# fpga_power.net
KiCad netlist of a schematic drawn in Altium Designer
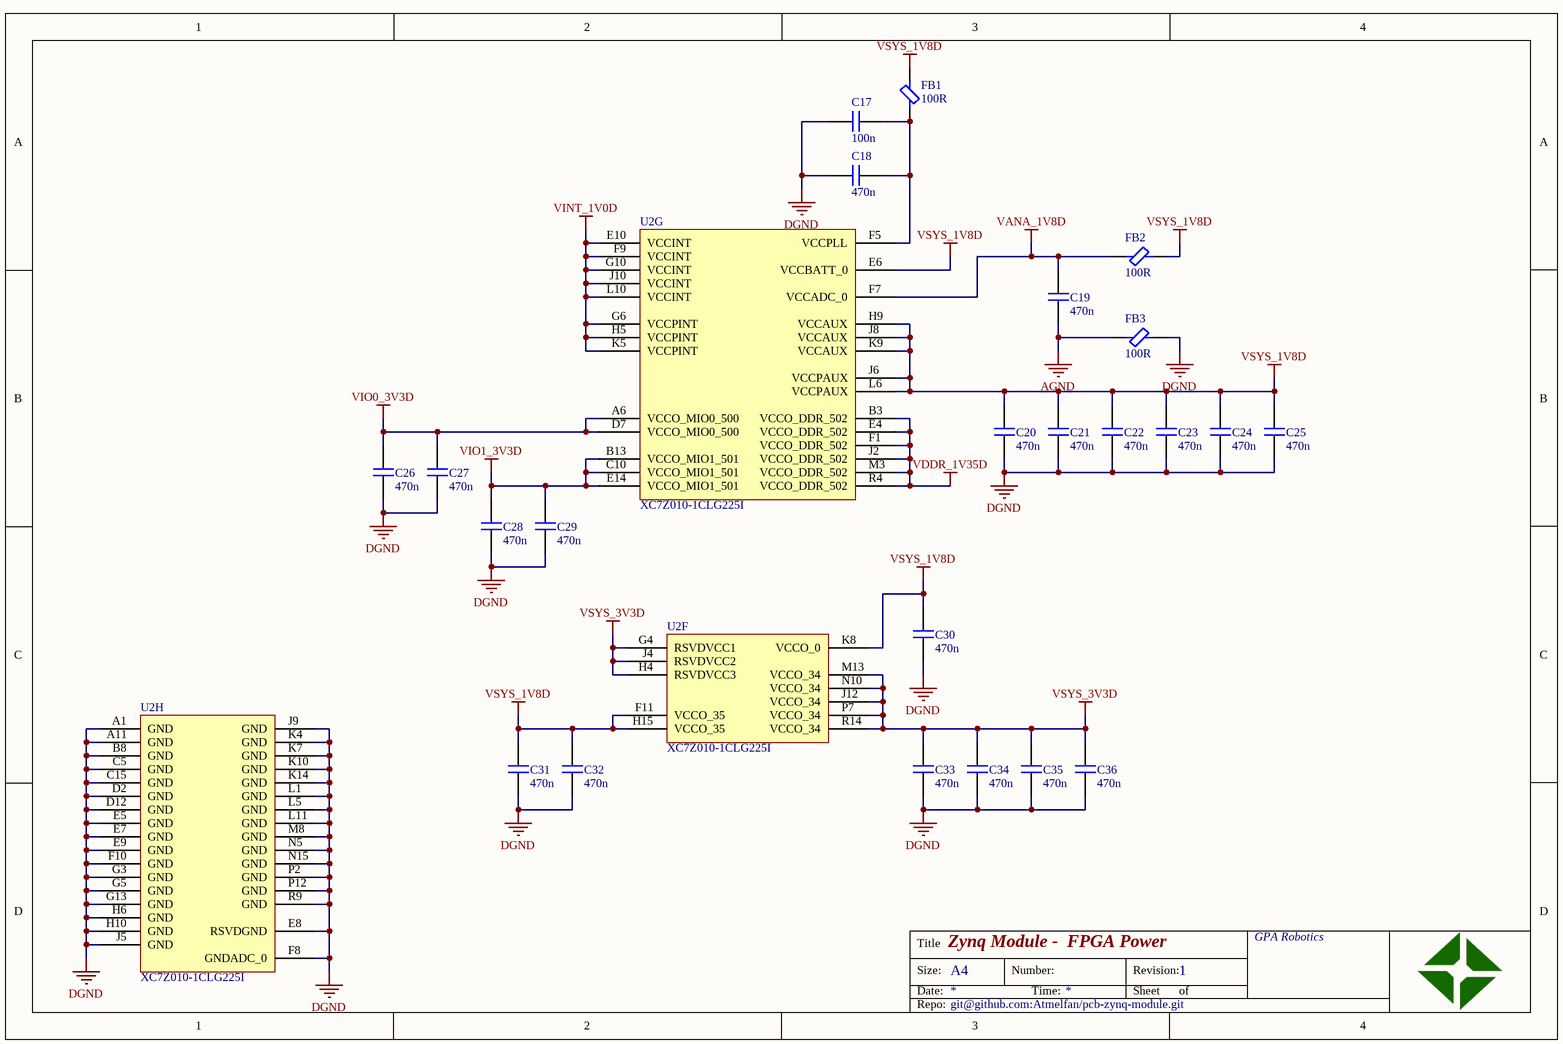
[diagram p0: fpga_power.SchDoc]

(export (version "E")
  (design (tool "Eeschema 10.0.6"))
  (components
    (comp (ref "C17")
      (value "100n")
      (footprint "CAPC2012X11N")
      (description "Capacitor")
      (fields (field (name "Comment") "cap"))
      (libsource (lib "lib_passives") (part "cap"))
    )
    (comp (ref "C18")
      (value "470n")
      (footprint "CAPC1608X08N")
      (description "Capacitor")
      (fields (field (name "Comment") "cap"))
      (libsource (lib "lib_passives") (part "cap"))
    )
    (comp (ref "C19")
      (value "470n")
      (footprint "CAPC1608X08N")
      (description "Capacitor")
      (fields (field (name "Comment") "cap"))
      (libsource (lib "lib_passives") (part "cap"))
    )
    (comp (ref "C20")
      (value "470n")
      (footprint "CAPC1608X08N")
      (description "Capacitor")
      (fields (field (name "Comment") "cap"))
      (libsource (lib "lib_passives") (part "cap"))
    )
    (comp (ref "C21")
      (value "470n")
      (footprint "CAPC1608X08N")
      (description "Capacitor")
      (fields (field (name "Comment") "cap"))
      (libsource (lib "lib_passives") (part "cap"))
    )
    (comp (ref "C22")
      (value "470n")
      (footprint "CAPC1608X08N")
      (description "Capacitor")
      (fields (field (name "Comment") "cap"))
      (libsource (lib "lib_passives") (part "cap"))
    )
    (comp (ref "C23")
      (value "470n")
      (footprint "CAPC1608X08N")
      (description "Capacitor")
      (fields (field (name "Comment") "cap"))
      (libsource (lib "lib_passives") (part "cap"))
    )
    (comp (ref "C24")
      (value "470n")
      (footprint "CAPC1608X08N")
      (description "Capacitor")
      (fields (field (name "Comment") "cap"))
      (libsource (lib "lib_passives") (part "cap"))
    )
    (comp (ref "C25")
      (value "470n")
      (footprint "CAPC1608X08N")
      (description "Capacitor")
      (fields (field (name "Comment") "cap"))
      (libsource (lib "lib_passives") (part "cap"))
    )
    (comp (ref "C26")
      (value "470n")
      (footprint "CAPC1608X08N")
      (description "Capacitor")
      (fields (field (name "Comment") "cap"))
      (libsource (lib "lib_passives") (part "cap"))
    )
    (comp (ref "C27")
      (value "470n")
      (footprint "CAPC1608X08N")
      (description "Capacitor")
      (fields (field (name "Comment") "cap"))
      (libsource (lib "lib_passives") (part "cap"))
    )
    (comp (ref "C28")
      (value "470n")
      (footprint "CAPC1608X08N")
      (description "Capacitor")
      (fields (field (name "Comment") "cap"))
      (libsource (lib "lib_passives") (part "cap"))
    )
    (comp (ref "C29")
      (value "470n")
      (footprint "CAPC1608X08N")
      (description "Capacitor")
      (fields (field (name "Comment") "cap"))
      (libsource (lib "lib_passives") (part "cap"))
    )
    (comp (ref "C30")
      (value "470n")
      (footprint "CAPC1608X08N")
      (description "Capacitor")
      (fields (field (name "Comment") "cap"))
      (libsource (lib "lib_passives") (part "cap"))
    )
    (comp (ref "C31")
      (value "470n")
      (footprint "CAPC1608X08N")
      (description "Capacitor")
      (fields (field (name "Comment") "cap"))
      (libsource (lib "lib_passives") (part "cap"))
    )
    (comp (ref "C32")
      (value "470n")
      (footprint "CAPC1608X08N")
      (description "Capacitor")
      (fields (field (name "Comment") "cap"))
      (libsource (lib "lib_passives") (part "cap"))
    )
    (comp (ref "C33")
      (value "470n")
      (footprint "CAPC1608X08N")
      (description "Capacitor")
      (fields (field (name "Comment") "cap"))
      (libsource (lib "lib_passives") (part "cap"))
    )
    (comp (ref "C34")
      (value "470n")
      (footprint "CAPC1608X08N")
      (description "Capacitor")
      (fields (field (name "Comment") "cap"))
      (libsource (lib "lib_passives") (part "cap"))
    )
    (comp (ref "C35")
      (value "470n")
      (footprint "CAPC1608X08N")
      (description "Capacitor")
      (fields (field (name "Comment") "cap"))
      (libsource (lib "lib_passives") (part "cap"))
    )
    (comp (ref "C36")
      (value "470n")
      (footprint "CAPC1608X08N")
      (description "Capacitor")
      (fields (field (name "Comment") "cap"))
      (libsource (lib "lib_passives") (part "cap"))
    )
    (comp (ref "FB1")
      (value "100R")
      (footprint "INDC1005X06N")
      (description "Inductor")
      (fields (field (name "Comment") "ferrite"))
      (libsource (lib "lib_passives") (part "ferrite"))
    )
    (comp (ref "FB2")
      (value "100R")
      (footprint "INDC1005X06N")
      (description "Inductor")
      (fields (field (name "Comment") "ferrite"))
      (libsource (lib "lib_passives") (part "ferrite"))
    )
    (comp (ref "FB3")
      (value "100R")
      (footprint "INDC1005X06N")
      (description "Inductor")
      (fields (field (name "Comment") "ferrite"))
      (libsource (lib "lib_passives") (part "ferrite"))
    )
    (comp (ref "U2")
      (value "XC7Z010-1CLG225I")
      (footprint "CLG225")
      (fields (field (name "GENERIC PART NUMBER") "XC7Z010"))
      (libsource (lib "Altium Content Vault") (part "XNLX-XC7Z010-CLG225"))
    )
  )
  (nets
    (net (code "1") (name "AGND") (class "Default")
      (node (ref "C19") (pin "1") (pinfunction "1_1") (pintype "passive"))
      (node (ref "FB3") (pin "2") (pinfunction "2_2") (pintype "passive"))
    )
    (net (code "2") (name "DGND") (class "Default")
      (node (ref "C17") (pin "1") (pinfunction "1_1") (pintype "passive"))
      (node (ref "C18") (pin "1") (pinfunction "1_1") (pintype "passive"))
      (node (ref "C20") (pin "1") (pinfunction "1_1") (pintype "passive"))
      (node (ref "C21") (pin "1") (pinfunction "1_1") (pintype "passive"))
      (node (ref "C22") (pin "1") (pinfunction "1_1") (pintype "passive"))
      (node (ref "C23") (pin "1") (pinfunction "1_1") (pintype "passive"))
      (node (ref "C24") (pin "1") (pinfunction "1_1") (pintype "passive"))
      (node (ref "C25") (pin "1") (pinfunction "1_1") (pintype "passive"))
      (node (ref "C26") (pin "1") (pinfunction "1_1") (pintype "passive"))
      (node (ref "C27") (pin "1") (pinfunction "1_1") (pintype "passive"))
      (node (ref "C28") (pin "1") (pinfunction "1_1") (pintype "passive"))
      (node (ref "C29") (pin "1") (pinfunction "1_1") (pintype "passive"))
      (node (ref "C30") (pin "1") (pinfunction "1_1") (pintype "passive"))
      (node (ref "C31") (pin "1") (pinfunction "1_1") (pintype "passive"))
      (node (ref "C32") (pin "1") (pinfunction "1_1") (pintype "passive"))
      (node (ref "C33") (pin "1") (pinfunction "1_1") (pintype "passive"))
      (node (ref "C34") (pin "1") (pinfunction "1_1") (pintype "passive"))
      (node (ref "C35") (pin "1") (pinfunction "1_1") (pintype "passive"))
      (node (ref "C36") (pin "1") (pinfunction "1_1") (pintype "passive"))
      (node (ref "FB3") (pin "1") (pinfunction "1_1") (pintype "passive"))
      (node (ref "U2") (pin "A1") (pinfunction "GND_A1") (pintype "power_in"))
      (node (ref "U2") (pin "A11") (pinfunction "GND_A11") (pintype "power_in"))
      (node (ref "U2") (pin "B8") (pinfunction "GND_B8") (pintype "power_in"))
      (node (ref "U2") (pin "C15") (pinfunction "GND_C15") (pintype "power_in"))
      (node (ref "U2") (pin "C5") (pinfunction "GND_C5") (pintype "power_in"))
      (node (ref "U2") (pin "D12") (pinfunction "GND_D12") (pintype "power_in"))
      (node (ref "U2") (pin "D2") (pinfunction "GND_D2") (pintype "power_in"))
      (node (ref "U2") (pin "E5") (pinfunction "GND_E5") (pintype "power_in"))
      (node (ref "U2") (pin "E7") (pinfunction "GND_E7") (pintype "power_in"))
      (node (ref "U2") (pin "E8") (pinfunction "RSVDGND_E8") (pintype "power_in"))
      (node (ref "U2") (pin "E9") (pinfunction "GND_E9") (pintype "power_in"))
      (node (ref "U2") (pin "F10") (pinfunction "GND_F10") (pintype "power_in"))
      (node (ref "U2") (pin "F8") (pinfunction "GNDADC_0_F8") (pintype "power_in"))
      (node (ref "U2") (pin "G13") (pinfunction "GND_G13") (pintype "power_in"))
      (node (ref "U2") (pin "G3") (pinfunction "GND_G3") (pintype "power_in"))
      (node (ref "U2") (pin "G5") (pinfunction "GND_G5") (pintype "power_in"))
      (node (ref "U2") (pin "H10") (pinfunction "GND_H10") (pintype "power_in"))
      (node (ref "U2") (pin "H6") (pinfunction "GND_H6") (pintype "power_in"))
      (node (ref "U2") (pin "J5") (pinfunction "GND_J5") (pintype "power_in"))
      (node (ref "U2") (pin "J9") (pinfunction "GND_J9") (pintype "power_in"))
      (node (ref "U2") (pin "K10") (pinfunction "GND_K10") (pintype "power_in"))
      (node (ref "U2") (pin "K14") (pinfunction "GND_K14") (pintype "power_in"))
      (node (ref "U2") (pin "K4") (pinfunction "GND_K4") (pintype "power_in"))
      (node (ref "U2") (pin "K7") (pinfunction "GND_K7") (pintype "power_in"))
      (node (ref "U2") (pin "L1") (pinfunction "GND_L1") (pintype "power_in"))
      (node (ref "U2") (pin "L11") (pinfunction "GND_L11") (pintype "power_in"))
      (node (ref "U2") (pin "L5") (pinfunction "GND_L5") (pintype "power_in"))
      (node (ref "U2") (pin "M8") (pinfunction "GND_M8") (pintype "power_in"))
      (node (ref "U2") (pin "N15") (pinfunction "GND_N15") (pintype "power_in"))
      (node (ref "U2") (pin "N5") (pinfunction "GND_N5") (pintype "power_in"))
      (node (ref "U2") (pin "P12") (pinfunction "GND_P12") (pintype "power_in"))
      (node (ref "U2") (pin "P2") (pinfunction "GND_P2") (pintype "power_in"))
      (node (ref "U2") (pin "R9") (pinfunction "GND_R9") (pintype "power_in"))
    )
    (net (code "3") (name "Net-(U2G-VCCPLL)") (class "Default")
      (node (ref "C17") (pin "2") (pinfunction "2_2") (pintype "passive"))
      (node (ref "C18") (pin "2") (pinfunction "2_2") (pintype "passive"))
      (node (ref "FB1") (pin "1") (pinfunction "1_1") (pintype "passive"))
      (node (ref "U2") (pin "F5") (pinfunction "VCCPLL_F5") (pintype "power_in"))
    )
    (net (code "4") (name "VANA_1V8D") (class "Default")
      (node (ref "C19") (pin "2") (pinfunction "2_2") (pintype "passive"))
      (node (ref "FB2") (pin "2") (pinfunction "2_2") (pintype "passive"))
      (node (ref "U2") (pin "F7") (pinfunction "VCCADC_0_F7") (pintype "power_in"))
    )
    (net (code "5") (name "VDDR_1V35D") (class "Default")
      (node (ref "U2") (pin "B3") (pinfunction "VCCO_DDR_502_B3") (pintype "power_in"))
      (node (ref "U2") (pin "E4") (pinfunction "VCCO_DDR_502_E4") (pintype "power_in"))
      (node (ref "U2") (pin "F1") (pinfunction "VCCO_DDR_502_F1") (pintype "power_in"))
      (node (ref "U2") (pin "J2") (pinfunction "VCCO_DDR_502_J2") (pintype "power_in"))
      (node (ref "U2") (pin "M3") (pinfunction "VCCO_DDR_502_M3") (pintype "power_in"))
      (node (ref "U2") (pin "R4") (pinfunction "VCCO_DDR_502_R4") (pintype "power_in"))
    )
    (net (code "6") (name "VINT_1V0D") (class "Default")
      (node (ref "U2") (pin "E10") (pinfunction "VCCINT_E10") (pintype "power_in"))
      (node (ref "U2") (pin "F9") (pinfunction "VCCINT_F9") (pintype "power_in"))
      (node (ref "U2") (pin "G10") (pinfunction "VCCINT_G10") (pintype "power_in"))
      (node (ref "U2") (pin "G6") (pinfunction "VCCPINT_G6") (pintype "power_in"))
      (node (ref "U2") (pin "H5") (pinfunction "VCCPINT_H5") (pintype "power_in"))
      (node (ref "U2") (pin "J10") (pinfunction "VCCINT_J10") (pintype "power_in"))
      (node (ref "U2") (pin "K5") (pinfunction "VCCPINT_K5") (pintype "power_in"))
      (node (ref "U2") (pin "L10") (pinfunction "VCCINT_L10") (pintype "power_in"))
    )
    (net (code "7") (name "VIO0_3V3D") (class "Default")
      (node (ref "C26") (pin "2") (pinfunction "2_2") (pintype "passive"))
      (node (ref "C27") (pin "2") (pinfunction "2_2") (pintype "passive"))
      (node (ref "U2") (pin "A6") (pinfunction "VCCO_MIO0_500_A6") (pintype "power_in"))
      (node (ref "U2") (pin "D7") (pinfunction "VCCO_MIO0_500_D7") (pintype "power_in"))
    )
    (net (code "8") (name "VIO1_3V3D") (class "Default")
      (node (ref "C28") (pin "2") (pinfunction "2_2") (pintype "passive"))
      (node (ref "C29") (pin "2") (pinfunction "2_2") (pintype "passive"))
      (node (ref "U2") (pin "B13") (pinfunction "VCCO_MIO1_501_B13") (pintype "power_in"))
      (node (ref "U2") (pin "C10") (pinfunction "VCCO_MIO1_501_C10") (pintype "power_in"))
      (node (ref "U2") (pin "E14") (pinfunction "VCCO_MIO1_501_E14") (pintype "power_in"))
    )
    (net (code "9") (name "VSYS_1V8D") (class "Default")
      (node (ref "C20") (pin "2") (pinfunction "2_2") (pintype "passive"))
      (node (ref "C21") (pin "2") (pinfunction "2_2") (pintype "passive"))
      (node (ref "C22") (pin "2") (pinfunction "2_2") (pintype "passive"))
      (node (ref "C23") (pin "2") (pinfunction "2_2") (pintype "passive"))
      (node (ref "C24") (pin "2") (pinfunction "2_2") (pintype "passive"))
      (node (ref "C25") (pin "2") (pinfunction "2_2") (pintype "passive"))
      (node (ref "C30") (pin "2") (pinfunction "2_2") (pintype "passive"))
      (node (ref "C31") (pin "2") (pinfunction "2_2") (pintype "passive"))
      (node (ref "C32") (pin "2") (pinfunction "2_2") (pintype "passive"))
      (node (ref "FB1") (pin "2") (pinfunction "2_2") (pintype "passive"))
      (node (ref "FB2") (pin "1") (pinfunction "1_1") (pintype "passive"))
      (node (ref "U2") (pin "E6") (pinfunction "VCCBATT_0_E6") (pintype "power_in"))
      (node (ref "U2") (pin "F11") (pinfunction "VCCO_35_F11") (pintype "power_in"))
      (node (ref "U2") (pin "H15") (pinfunction "VCCO_35_H15") (pintype "power_in"))
      (node (ref "U2") (pin "H9") (pinfunction "VCCAUX_H9") (pintype "power_in"))
      (node (ref "U2") (pin "J6") (pinfunction "VCCPAUX_J6") (pintype "power_in"))
      (node (ref "U2") (pin "J8") (pinfunction "VCCAUX_J8") (pintype "power_in"))
      (node (ref "U2") (pin "K8") (pinfunction "VCCO_0_K8") (pintype "power_in"))
      (node (ref "U2") (pin "K9") (pinfunction "VCCAUX_K9") (pintype "power_in"))
      (node (ref "U2") (pin "L6") (pinfunction "VCCPAUX_L6") (pintype "power_in"))
    )
    (net (code "10") (name "VSYS_3V3D") (class "Default")
      (node (ref "C33") (pin "2") (pinfunction "2_2") (pintype "passive"))
      (node (ref "C34") (pin "2") (pinfunction "2_2") (pintype "passive"))
      (node (ref "C35") (pin "2") (pinfunction "2_2") (pintype "passive"))
      (node (ref "C36") (pin "2") (pinfunction "2_2") (pintype "passive"))
      (node (ref "U2") (pin "G4") (pinfunction "RSVDVCC1_G4") (pintype "power_in"))
      (node (ref "U2") (pin "H4") (pinfunction "RSVDVCC3_H4") (pintype "power_in"))
      (node (ref "U2") (pin "J12") (pinfunction "VCCO_34_J12") (pintype "power_in"))
      (node (ref "U2") (pin "J4") (pinfunction "RSVDVCC2_J4") (pintype "power_in"))
      (node (ref "U2") (pin "M13") (pinfunction "VCCO_34_M13") (pintype "power_in"))
      (node (ref "U2") (pin "N10") (pinfunction "VCCO_34_N10") (pintype "power_in"))
      (node (ref "U2") (pin "P7") (pinfunction "VCCO_34_P7") (pintype "power_in"))
      (node (ref "U2") (pin "R14") (pinfunction "VCCO_34_R14") (pintype "power_in"))
    )
  )
)
